# eindwerk_board.net
KiCad netlist of a schematic drawn in EAGLE
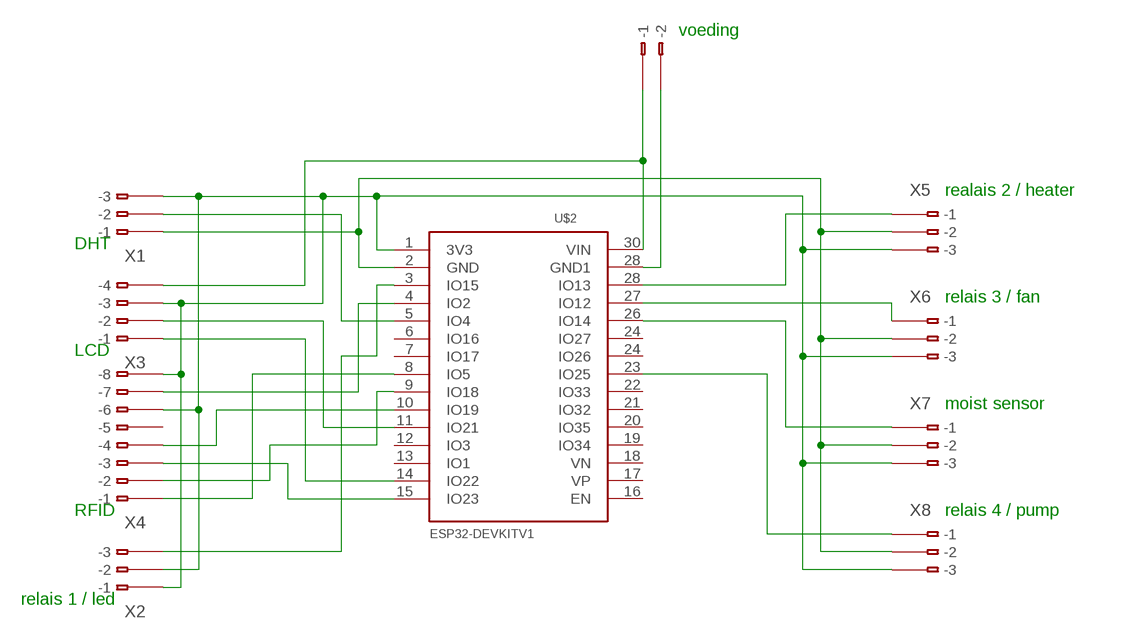
[diagram p0: schematic, sheet 1]

(export (version "E")
  (design (tool "Eeschema 10.0.6"))
  (components
    (comp (ref "U$2")
      (value "ESP32DEVKITV1")
      (footprint "eagle-import:ESP32-DEVKITV1")
      (libsource (lib "eagle-import") (part "ESP32DEVKITV1"))
    )
    (comp (ref "VOEDING")
      (value "233-102")
      (footprint "eagle-import:233-102")
      (libsource (lib "eagle-import") (part "233-102"))
    )
    (comp (ref "X1")
      (value "233-103")
      (footprint "eagle-import:233-103")
      (libsource (lib "eagle-import") (part "233-103"))
    )
    (comp (ref "X2")
      (value "233-103")
      (footprint "eagle-import:233-103")
      (libsource (lib "eagle-import") (part "233-103"))
    )
    (comp (ref "X3")
      (value "233-104")
      (footprint "eagle-import:233-104")
      (libsource (lib "eagle-import") (part "233-104"))
    )
    (comp (ref "X4")
      (value "233-108")
      (footprint "eagle-import:233-108")
      (libsource (lib "eagle-import") (part "233-108"))
    )
    (comp (ref "X5")
      (value "233-103")
      (footprint "eagle-import:233-103")
      (libsource (lib "eagle-import") (part "233-103"))
    )
    (comp (ref "X6")
      (value "233-103")
      (footprint "eagle-import:233-103")
      (libsource (lib "eagle-import") (part "233-103"))
    )
    (comp (ref "X7")
      (value "233-103")
      (footprint "eagle-import:233-103")
      (libsource (lib "eagle-import") (part "233-103"))
    )
    (comp (ref "X8")
      (value "233-103")
      (footprint "eagle-import:233-103")
      (libsource (lib "eagle-import") (part "233-103"))
    )
  )
  (nets
    (net (code "1") (name "Net-(U$2-3V3)") (class "Default")
      (node (ref "U$2") (pin "1") (pinfunction "3V3_1") (pintype "bidirectional"))
      (node (ref "X1") (pin "B3") (pinfunction "B-3_B3") (pintype "passive"))
      (node (ref "X2") (pin "B1") (pinfunction "B-1_B1") (pintype "passive"))
      (node (ref "X2") (pin "B2") (pinfunction "B-2_B2") (pintype "passive"))
      (node (ref "X3") (pin "B3") (pinfunction "B-3_B3") (pintype "passive"))
      (node (ref "X4") (pin "B6") (pinfunction "B-6_B6") (pintype "passive"))
      (node (ref "X4") (pin "B8") (pinfunction "B-8_B8") (pintype "passive"))
      (node (ref "X5") (pin "B3") (pinfunction "B-3_B3") (pintype "passive"))
      (node (ref "X6") (pin "B3") (pinfunction "B-3_B3") (pintype "passive"))
      (node (ref "X7") (pin "B3") (pinfunction "B-3_B3") (pintype "passive"))
      (node (ref "X8") (pin "B3") (pinfunction "B-3_B3") (pintype "passive"))
    )
    (net (code "2") (name "Net-(U$2-GND)") (class "Default")
      (node (ref "U$2") (pin "2") (pinfunction "GND_2") (pintype "bidirectional"))
      (node (ref "X1") (pin "B1") (pinfunction "B-1_B1") (pintype "passive"))
      (node (ref "X5") (pin "B2") (pinfunction "B-2_B2") (pintype "passive"))
      (node (ref "X6") (pin "B2") (pinfunction "B-2_B2") (pintype "passive"))
      (node (ref "X7") (pin "B2") (pinfunction "B-2_B2") (pintype "passive"))
      (node (ref "X8") (pin "B2") (pinfunction "B-2_B2") (pintype "passive"))
    )
    (net (code "3") (name "Net-(U$2-GND1)") (class "Default")
      (node (ref "U$2") (pin "28") (pinfunction "GND1_28") (pintype "bidirectional"))
      (node (ref "VOEDING") (pin "B2") (pinfunction "B-2_B2") (pintype "passive"))
    )
    (net (code "4") (name "Net-(U$2-IO2)") (class "Default")
      (node (ref "U$2") (pin "4") (pinfunction "IO2_4") (pintype "bidirectional"))
      (node (ref "X4") (pin "B7") (pinfunction "B-7_B7") (pintype "passive"))
    )
    (net (code "5") (name "Net-(U$2-IO4)") (class "Default")
      (node (ref "U$2") (pin "5") (pinfunction "IO4_5") (pintype "bidirectional"))
      (node (ref "X1") (pin "B2") (pinfunction "B-2_B2") (pintype "passive"))
    )
    (net (code "6") (name "Net-(U$2-IO5)") (class "Default")
      (node (ref "U$2") (pin "8") (pinfunction "IO5_8") (pintype "bidirectional"))
      (node (ref "X4") (pin "B1") (pinfunction "B-1_B1") (pintype "passive"))
    )
    (net (code "7") (name "Net-(U$2-IO12)") (class "Default")
      (node (ref "U$2") (pin "27") (pinfunction "IO12_27") (pintype "bidirectional"))
      (node (ref "X6") (pin "B1") (pinfunction "B-1_B1") (pintype "passive"))
    )
    (net (code "8") (name "Net-(U$2-IO13)") (class "Default")
      (node (ref "U$2") (pin "28") (pinfunction "IO13_28") (pintype "bidirectional"))
      (node (ref "X5") (pin "B1") (pinfunction "B-1_B1") (pintype "passive"))
    )
    (net (code "9") (name "Net-(U$2-IO14)") (class "Default")
      (node (ref "U$2") (pin "26") (pinfunction "IO14_26") (pintype "bidirectional"))
      (node (ref "X7") (pin "B1") (pinfunction "B-1_B1") (pintype "passive"))
    )
    (net (code "10") (name "Net-(U$2-IO15)") (class "Default")
      (node (ref "U$2") (pin "3") (pinfunction "IO15_3") (pintype "bidirectional"))
      (node (ref "X2") (pin "B3") (pinfunction "B-3_B3") (pintype "passive"))
    )
    (net (code "11") (name "Net-(U$2-IO18)") (class "Default")
      (node (ref "U$2") (pin "9") (pinfunction "IO18_9") (pintype "bidirectional"))
      (node (ref "X4") (pin "B2") (pinfunction "B-2_B2") (pintype "passive"))
    )
    (net (code "12") (name "Net-(U$2-IO19)") (class "Default")
      (node (ref "U$2") (pin "10") (pinfunction "IO19_10") (pintype "bidirectional"))
      (node (ref "X4") (pin "B4") (pinfunction "B-4_B4") (pintype "passive"))
    )
    (net (code "13") (name "Net-(U$2-IO21)") (class "Default")
      (node (ref "U$2") (pin "11") (pinfunction "IO21_11") (pintype "bidirectional"))
      (node (ref "X3") (pin "B2") (pinfunction "B-2_B2") (pintype "passive"))
    )
    (net (code "14") (name "Net-(U$2-IO22)") (class "Default")
      (node (ref "U$2") (pin "14") (pinfunction "IO22_14") (pintype "bidirectional"))
      (node (ref "X3") (pin "B1") (pinfunction "B-1_B1") (pintype "passive"))
    )
    (net (code "15") (name "Net-(U$2-IO23)") (class "Default")
      (node (ref "U$2") (pin "15") (pinfunction "IO23_15") (pintype "bidirectional"))
      (node (ref "X4") (pin "B3") (pinfunction "B-3_B3") (pintype "passive"))
    )
    (net (code "16") (name "Net-(U$2-IO25)") (class "Default")
      (node (ref "U$2") (pin "23") (pinfunction "IO25_23") (pintype "bidirectional"))
      (node (ref "X8") (pin "B1") (pinfunction "B-1_B1") (pintype "passive"))
    )
    (net (code "17") (name "Net-(U$2-VIN)") (class "Default")
      (node (ref "U$2") (pin "30") (pinfunction "VIN_30") (pintype "bidirectional"))
      (node (ref "VOEDING") (pin "B1") (pinfunction "B-1_B1") (pintype "passive"))
      (node (ref "X3") (pin "B4") (pinfunction "B-4_B4") (pintype "passive"))
    )
    (net (code "18") (name "unconnected-(U$2-EN-Pad16)") (class "Default")
      (node (ref "U$2") (pin "16") (pinfunction "EN_16") (pintype "bidirectional"))
    )
    (net (code "19") (name "unconnected-(U$2-IO1-Pad13)") (class "Default")
      (node (ref "U$2") (pin "13") (pinfunction "IO1_13") (pintype "bidirectional"))
    )
    (net (code "20") (name "unconnected-(U$2-IO3-Pad12)") (class "Default")
      (node (ref "U$2") (pin "12") (pinfunction "IO3_12") (pintype "bidirectional"))
    )
    (net (code "21") (name "unconnected-(U$2-IO16-Pad6)") (class "Default")
      (node (ref "U$2") (pin "6") (pinfunction "IO16_6") (pintype "bidirectional"))
    )
    (net (code "22") (name "unconnected-(U$2-IO17-Pad7)") (class "Default")
      (node (ref "U$2") (pin "7") (pinfunction "IO17_7") (pintype "bidirectional"))
    )
    (net (code "23") (name "unconnected-(U$2-IO26-Pad24)") (class "Default")
      (node (ref "U$2") (pin "24") (pinfunction "IO26_24") (pintype "bidirectional"))
    )
    (net (code "24") (name "unconnected-(U$2-IO27-Pad24)") (class "Default")
      (node (ref "U$2") (pin "24") (pinfunction "IO27_24") (pintype "bidirectional"))
    )
    (net (code "25") (name "unconnected-(U$2-IO32-Pad21)") (class "Default")
      (node (ref "U$2") (pin "21") (pinfunction "IO32_21") (pintype "bidirectional"))
    )
    (net (code "26") (name "unconnected-(U$2-IO33-Pad22)") (class "Default")
      (node (ref "U$2") (pin "22") (pinfunction "IO33_22") (pintype "bidirectional"))
    )
    (net (code "27") (name "unconnected-(U$2-IO34-Pad19)") (class "Default")
      (node (ref "U$2") (pin "19") (pinfunction "IO34_19") (pintype "bidirectional"))
    )
    (net (code "28") (name "unconnected-(U$2-IO35-Pad20)") (class "Default")
      (node (ref "U$2") (pin "20") (pinfunction "IO35_20") (pintype "bidirectional"))
    )
    (net (code "29") (name "unconnected-(U$2-VN-Pad18)") (class "Default")
      (node (ref "U$2") (pin "18") (pinfunction "VN_18") (pintype "bidirectional"))
    )
    (net (code "30") (name "unconnected-(U$2-VP-Pad17)") (class "Default")
      (node (ref "U$2") (pin "17") (pinfunction "VP_17") (pintype "bidirectional"))
    )
    (net (code "31") (name "unconnected-(VOEDING--1-PadA1)") (class "Default")
      (node (ref "VOEDING") (pin "A1") (pinfunction "-1_A1") (pintype "passive"))
    )
    (net (code "32") (name "unconnected-(VOEDING--2-PadA2)") (class "Default")
      (node (ref "VOEDING") (pin "A2") (pinfunction "-2_A2") (pintype "passive"))
    )
    (net (code "33") (name "unconnected-(X1--1-PadA1)") (class "Default")
      (node (ref "X1") (pin "A1") (pinfunction "-1_A1") (pintype "passive"))
    )
    (net (code "34") (name "unconnected-(X1--2-PadA2)") (class "Default")
      (node (ref "X1") (pin "A2") (pinfunction "-2_A2") (pintype "passive"))
    )
    (net (code "35") (name "unconnected-(X1--3-PadA3)") (class "Default")
      (node (ref "X1") (pin "A3") (pinfunction "-3_A3") (pintype "passive"))
    )
    (net (code "36") (name "unconnected-(X2--1-PadA1)") (class "Default")
      (node (ref "X2") (pin "A1") (pinfunction "-1_A1") (pintype "passive"))
    )
    (net (code "37") (name "unconnected-(X2--2-PadA2)") (class "Default")
      (node (ref "X2") (pin "A2") (pinfunction "-2_A2") (pintype "passive"))
    )
    (net (code "38") (name "unconnected-(X2--3-PadA3)") (class "Default")
      (node (ref "X2") (pin "A3") (pinfunction "-3_A3") (pintype "passive"))
    )
    (net (code "39") (name "unconnected-(X3--1-PadA1)") (class "Default")
      (node (ref "X3") (pin "A1") (pinfunction "-1_A1") (pintype "passive"))
    )
    (net (code "40") (name "unconnected-(X3--2-PadA2)") (class "Default")
      (node (ref "X3") (pin "A2") (pinfunction "-2_A2") (pintype "passive"))
    )
    (net (code "41") (name "unconnected-(X3--3-PadA3)") (class "Default")
      (node (ref "X3") (pin "A3") (pinfunction "-3_A3") (pintype "passive"))
    )
    (net (code "42") (name "unconnected-(X3--4-PadA4)") (class "Default")
      (node (ref "X3") (pin "A4") (pinfunction "-4_A4") (pintype "passive"))
    )
    (net (code "43") (name "unconnected-(X4--1-PadA1)") (class "Default")
      (node (ref "X4") (pin "A1") (pinfunction "-1_A1") (pintype "passive"))
    )
    (net (code "44") (name "unconnected-(X4--2-PadA2)") (class "Default")
      (node (ref "X4") (pin "A2") (pinfunction "-2_A2") (pintype "passive"))
    )
    (net (code "45") (name "unconnected-(X4--3-PadA3)") (class "Default")
      (node (ref "X4") (pin "A3") (pinfunction "-3_A3") (pintype "passive"))
    )
    (net (code "46") (name "unconnected-(X4--4-PadA4)") (class "Default")
      (node (ref "X4") (pin "A4") (pinfunction "-4_A4") (pintype "passive"))
    )
    (net (code "47") (name "unconnected-(X4--5-PadA5)") (class "Default")
      (node (ref "X4") (pin "A5") (pinfunction "-5_A5") (pintype "passive"))
    )
    (net (code "48") (name "unconnected-(X4--6-PadA6)") (class "Default")
      (node (ref "X4") (pin "A6") (pinfunction "-6_A6") (pintype "passive"))
    )
    (net (code "49") (name "unconnected-(X4--7-PadA7)") (class "Default")
      (node (ref "X4") (pin "A7") (pinfunction "-7_A7") (pintype "passive"))
    )
    (net (code "50") (name "unconnected-(X4--8-PadA8)") (class "Default")
      (node (ref "X4") (pin "A8") (pinfunction "-8_A8") (pintype "passive"))
    )
    (net (code "51") (name "unconnected-(X4-B-5-PadB5)") (class "Default")
      (node (ref "X4") (pin "B5") (pinfunction "B-5_B5") (pintype "passive"))
    )
    (net (code "52") (name "unconnected-(X5--1-PadA1)") (class "Default")
      (node (ref "X5") (pin "A1") (pinfunction "-1_A1") (pintype "passive"))
    )
    (net (code "53") (name "unconnected-(X5--2-PadA2)") (class "Default")
      (node (ref "X5") (pin "A2") (pinfunction "-2_A2") (pintype "passive"))
    )
    (net (code "54") (name "unconnected-(X5--3-PadA3)") (class "Default")
      (node (ref "X5") (pin "A3") (pinfunction "-3_A3") (pintype "passive"))
    )
    (net (code "55") (name "unconnected-(X6--1-PadA1)") (class "Default")
      (node (ref "X6") (pin "A1") (pinfunction "-1_A1") (pintype "passive"))
    )
    (net (code "56") (name "unconnected-(X6--2-PadA2)") (class "Default")
      (node (ref "X6") (pin "A2") (pinfunction "-2_A2") (pintype "passive"))
    )
    (net (code "57") (name "unconnected-(X6--3-PadA3)") (class "Default")
      (node (ref "X6") (pin "A3") (pinfunction "-3_A3") (pintype "passive"))
    )
    (net (code "58") (name "unconnected-(X7--1-PadA1)") (class "Default")
      (node (ref "X7") (pin "A1") (pinfunction "-1_A1") (pintype "passive"))
    )
    (net (code "59") (name "unconnected-(X7--2-PadA2)") (class "Default")
      (node (ref "X7") (pin "A2") (pinfunction "-2_A2") (pintype "passive"))
    )
    (net (code "60") (name "unconnected-(X7--3-PadA3)") (class "Default")
      (node (ref "X7") (pin "A3") (pinfunction "-3_A3") (pintype "passive"))
    )
    (net (code "61") (name "unconnected-(X8--1-PadA1)") (class "Default")
      (node (ref "X8") (pin "A1") (pinfunction "-1_A1") (pintype "passive"))
    )
    (net (code "62") (name "unconnected-(X8--2-PadA2)") (class "Default")
      (node (ref "X8") (pin "A2") (pinfunction "-2_A2") (pintype "passive"))
    )
    (net (code "63") (name "unconnected-(X8--3-PadA3)") (class "Default")
      (node (ref "X8") (pin "A3") (pinfunction "-3_A3") (pintype "passive"))
    )
  )
)
